# 5V0_SYS_SUPPLY.net
KiCad netlist of a schematic drawn in Altium Designer
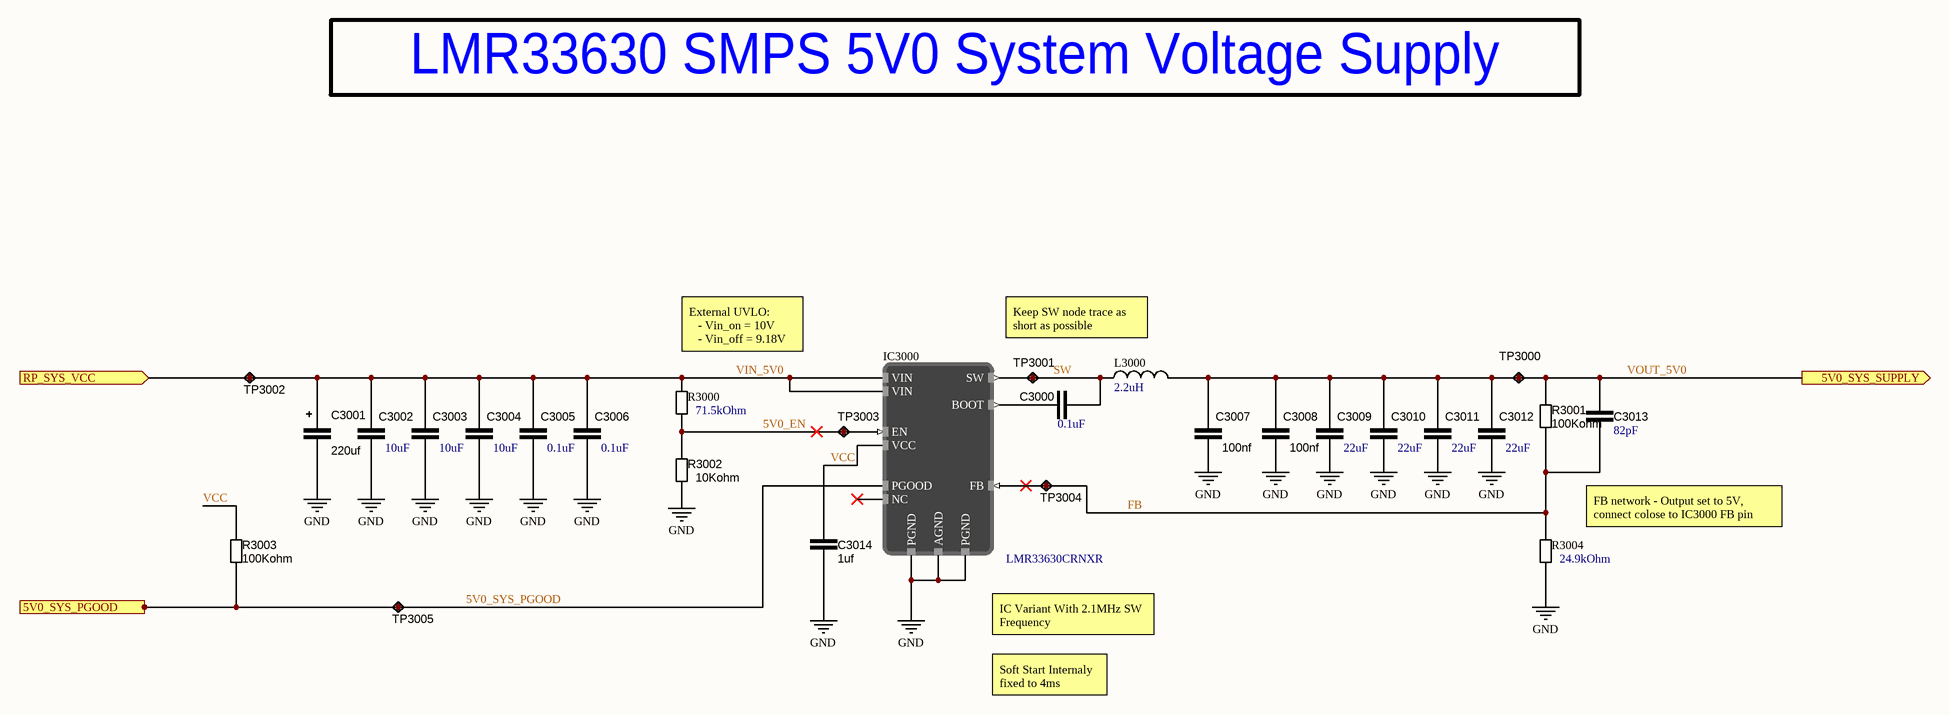
[diagram p0: 5V0_SYS_SUPPLY.SchDoc]

(export (version "E")
  (design (tool "Eeschema 10.0.6"))
  (components
    (comp (ref "C3000")
      (value "0.1uF")
      (footprint "CAP_0603")
      (description "CAP CER 0.1UF 50V X7R 0603")
      (fields (field (name "DIGIKEY PART NUMBER") "1276-1000-1-ND"))
      (libsource (lib "CapacitorsIntegrated") (part "C000018"))
    )
    (comp (ref "C3001")
      (value "220uf")
      (footprint "CAPAE109103X103M")
      (description "CAP ALUM 220UF 20% 50V SMD")
      (fields (field (name "DIGIKEY PART NUMBER") "493-9426-1-ND"))
      (libsource (lib "CapacitorsIntegrated") (part "C000019"))
    )
    (comp (ref "C3002")
      (value "10uF")
      (footprint "CAP_1206")
      (description "CAP CER 10UF 50V X7R 1206")
      (fields (field (name "DIGIKEY PART NUMBER") "1276-6767-1-ND"))
      (libsource (lib "CapacitorsIntegrated") (part "C000017"))
    )
    (comp (ref "C3003")
      (value "10uF")
      (footprint "CAP_1206")
      (description "CAP CER 10UF 50V X7R 1206")
      (fields (field (name "DIGIKEY PART NUMBER") "1276-6767-1-ND"))
      (libsource (lib "CapacitorsIntegrated") (part "C000017"))
    )
    (comp (ref "C3004")
      (value "10uF")
      (footprint "CAP_1206")
      (description "CAP CER 10UF 50V X7R 1206")
      (fields (field (name "DIGIKEY PART NUMBER") "1276-6767-1-ND"))
      (libsource (lib "CapacitorsIntegrated") (part "C000017"))
    )
    (comp (ref "C3005")
      (value "0.1uF")
      (footprint "CAP_0603")
      (description "CAP CER 0.1UF 50V X7R 0603")
      (fields (field (name "DIGIKEY PART NUMBER") "1276-1000-1-ND"))
      (libsource (lib "") (part "C000018_1"))
    )
    (comp (ref "C3006")
      (value "0.1uF")
      (footprint "CAP_0603")
      (description "CAP CER 0.1UF 50V X7R 0603")
      (fields (field (name "DIGIKEY PART NUMBER") "1276-1000-1-ND"))
      (libsource (lib "") (part "C000018_1"))
    )
    (comp (ref "C3007")
      (value "100nf")
      (footprint "CAP_0603")
      (description "CAP CER 100nF 0603 25V X7R")
      (libsource (lib "CapacitorsIntegrated") (part "C000007"))
    )
    (comp (ref "C3008")
      (value "100nf")
      (footprint "CAP_0603")
      (description "CAP CER 100nF 0603 25V X7R")
      (libsource (lib "CapacitorsIntegrated") (part "C000007"))
    )
    (comp (ref "C3009")
      (value "22uF")
      (footprint "CAP_1206")
      (description "22 µF ±10% 25V Ceramic Capacitor X5R 1206 (3216 Metric)")
      (fields (field (name "DIGIKEY PART NUMBER") "1276-3047-1-ND"))
      (libsource (lib "CapacitorsIntegrated") (part "C000020"))
    )
    (comp (ref "C3010")
      (value "22uF")
      (footprint "CAP_1206")
      (description "22 µF ±10% 25V Ceramic Capacitor X5R 1206 (3216 Metric)")
      (fields (field (name "DIGIKEY PART NUMBER") "1276-3047-1-ND"))
      (libsource (lib "CapacitorsIntegrated") (part "C000020"))
    )
    (comp (ref "C3011")
      (value "22uF")
      (footprint "CAP_1206")
      (description "22 µF ±10% 25V Ceramic Capacitor X5R 1206 (3216 Metric)")
      (fields (field (name "DIGIKEY PART NUMBER") "1276-3047-1-ND"))
      (libsource (lib "CapacitorsIntegrated") (part "C000020"))
    )
    (comp (ref "C3012")
      (value "22uF")
      (footprint "CAP_1206")
      (description "22 µF ±10% 25V Ceramic Capacitor X5R 1206 (3216 Metric)")
      (fields (field (name "DIGIKEY PART NUMBER") "1276-3047-1-ND"))
      (libsource (lib "CapacitorsIntegrated") (part "C000020"))
    )
    (comp (ref "C3013")
      (value "82pF")
      (footprint "CAP_0603")
      (description "82 pF ±1% 25V Ceramic Capacitor C0G, NP0 0603 (1608 Metric)")
      (fields (field (name "DIGIKEY PART NUMBER") "478-KGM15ACG1E820FTCT-ND"))
      (libsource (lib "CapacitorsIntegrated") (part "C000021"))
    )
    (comp (ref "C3014")
      (value "1uf")
      (footprint "CAP_0603")
      (description "CAP CER 1uF 10V X7R 0603")
      (fields (field (name "DIGIKEY PART NUMBER") "1276-1946-2-ND"))
      (libsource (lib "CapacitorsIntegrated") (part "C000011"))
    )
    (comp (ref "IC3000")
      (value "LMR33630CRNXR")
      (footprint "VQFN-HR")
      (description "Buck Switching Regulator IC Positive Adjustable 1V 1 Output 3A 12-PowerVFQFN")
      (fields
        (field (name "DIGIKEY PART NUMBER") "296-49768-1-ND")
        (field (name "MOUSER PART NUMBER") "595-LMR33630CRNXR")
      )
      (libsource (lib "IntegratedCircuits") (part "LMR33630CRNXR"))
    )
    (comp (ref "L3000")
      (value "2.2uH")
      (footprint "INDP_518X518")
      (description "FIXED IND 2.2UH 4.2A 50.1MOHM SM")
      (fields (field (name "DIGIKEY PART NUMBER") "541-1088-1-ND"))
      (libsource (lib "InductorIntegrated") (part "L000012"))
    )
    (comp (ref "R3000")
      (value "71.5kOhm")
      (footprint "RES_0603")
      (description "71.5 kOhms ±1% 0.1W, 1/10W Chip Resistor 0603 (1608 Metric) Moisture Resistant Thick Film")
      (fields (field (name "DIGIKEY PART NUMBER") "311-71.5KHRCT-ND"))
      (libsource (lib "ResistorsIntegrated") (part "R000022"))
    )
    (comp (ref "R3001")
      (value "100Kohm")
      (footprint "RES_0603")
      (description "RES 100K OHM 1% 1/10W 0603")
      (libsource (lib "ResistorsIntegrated") (part "R000006"))
    )
    (comp (ref "R3002")
      (value "10Kohm")
      (footprint "RES_0603")
      (description "RES 10K OHM 1% 1/10W 0603")
      (libsource (lib "ResistorsIntegrated") (part "R000001"))
    )
    (comp (ref "R3003")
      (value "100Kohm")
      (footprint "RES_0603")
      (description "RES 100K OHM 1% 1/10W 0603")
      (libsource (lib "ResistorsIntegrated") (part "R000006"))
    )
    (comp (ref "R3004")
      (value "24.9kOhm")
      (footprint "RES_0603")
      (description "24.9 kOhms ±1% 0.1W, 1/10W Chip Resistor 0603 (1608 Metric) Automotive AEC-Q200 Thick Film")
      (fields (field (name "DIGIKEY PART NUMBER") "P24.9KHCT-ND"))
      (libsource (lib "ResistorsIntegrated") (part "R000017"))
    )
    (comp (ref "TP3000")
      (value "Test point")
      (footprint "TestPoint")
      (description "Test point 1mm")
      (libsource (lib "IntegratedCircuits") (part "TP002"))
    )
    (comp (ref "TP3001")
      (value "Test point")
      (footprint "TestPoint")
      (description "Test point 1mm")
      (libsource (lib "IntegratedCircuits") (part "TP002"))
    )
    (comp (ref "TP3002")
      (value "Test point")
      (footprint "TestPoint")
      (description "Test point 1mm")
      (libsource (lib "IntegratedCircuits") (part "TP002"))
    )
    (comp (ref "TP3003")
      (value "Test point")
      (footprint "TestPoint")
      (description "Test point 1mm")
      (libsource (lib "IntegratedCircuits") (part "TP002"))
    )
    (comp (ref "TP3004")
      (value "Test point")
      (footprint "TestPoint")
      (description "Test point 1mm")
      (libsource (lib "IntegratedCircuits") (part "TP002"))
    )
    (comp (ref "TP3005")
      (value "Test point")
      (footprint "TestPoint")
      (description "Test point 1mm")
      (libsource (lib "IntegratedCircuits") (part "TP002"))
    )
  )
  (nets
    (net (code "1") (name "/5V0_EN") (class "Default")
      (node (ref "IC3000") (pin "9") (pinfunction "EN_9") (pintype "input"))
      (node (ref "R3000") (pin "1") (pinfunction "1_1") (pintype "passive"))
      (node (ref "R3002") (pin "2") (pinfunction "2_2") (pintype "passive"))
      (node (ref "TP3003") (pin "1") (pinfunction "1_1") (pintype "passive"))
    )
    (net (code "2") (name "/5V0_SYS_PGOOD") (class "Default")
      (node (ref "IC3000") (pin "8") (pinfunction "PGOOD_8") (pintype "open_collector"))
      (node (ref "R3003") (pin "1") (pinfunction "1_1") (pintype "passive"))
      (node (ref "TP3005") (pin "1") (pinfunction "1_1") (pintype "passive"))
    )
    (net (code "3") (name "/FB") (class "Default")
      (node (ref "C3013") (pin "1") (pinfunction "1_1") (pintype "passive"))
      (node (ref "IC3000") (pin "7") (pinfunction "FB_7") (pintype "input"))
      (node (ref "R3001") (pin "1") (pinfunction "1_1") (pintype "passive"))
      (node (ref "R3004") (pin "2") (pinfunction "2_2") (pintype "passive"))
      (node (ref "TP3004") (pin "1") (pinfunction "1_1") (pintype "passive"))
    )
    (net (code "4") (name "/SW") (class "Default")
      (node (ref "C3000") (pin "2") (pinfunction "2_2") (pintype "passive"))
      (node (ref "IC3000") (pin "12") (pinfunction "SW_12") (pintype "output"))
      (node (ref "L3000") (pin "1") (pinfunction "1_1") (pintype "passive"))
      (node (ref "TP3001") (pin "1") (pinfunction "1_1") (pintype "passive"))
    )
    (net (code "5") (name "/VCC") (class "Default")
      (node (ref "C3014") (pin "2") (pinfunction "2_2") (pintype "passive"))
      (node (ref "IC3000") (pin "5") (pinfunction "VCC_5") (pintype "power_in"))
      (node (ref "R3003") (pin "2") (pinfunction "2_2") (pintype "passive"))
    )
    (net (code "6") (name "/VIN_5V0") (class "Default")
      (node (ref "C3001") (pin "2") (pinfunction "2_2") (pintype "passive"))
      (node (ref "C3002") (pin "2") (pinfunction "2_2") (pintype "passive"))
      (node (ref "C3003") (pin "2") (pinfunction "2_2") (pintype "passive"))
      (node (ref "C3004") (pin "2") (pinfunction "2_2") (pintype "passive"))
      (node (ref "C3005") (pin "2") (pinfunction "2_2") (pintype "passive"))
      (node (ref "C3006") (pin "2") (pinfunction "2_2") (pintype "passive"))
      (node (ref "IC3000") (pin "10") (pinfunction "VIN_10") (pintype "passive"))
      (node (ref "IC3000") (pin "2") (pinfunction "VIN_2") (pintype "passive"))
      (node (ref "R3000") (pin "2") (pinfunction "2_2") (pintype "passive"))
      (node (ref "TP3002") (pin "1") (pinfunction "1_1") (pintype "passive"))
    )
    (net (code "7") (name "/VOUT_5V0") (class "Default")
      (node (ref "C3007") (pin "2") (pinfunction "2_2") (pintype "passive"))
      (node (ref "C3008") (pin "2") (pinfunction "2_2") (pintype "passive"))
      (node (ref "C3009") (pin "2") (pinfunction "2_2") (pintype "passive"))
      (node (ref "C3010") (pin "2") (pinfunction "2_2") (pintype "passive"))
      (node (ref "C3011") (pin "2") (pinfunction "2_2") (pintype "passive"))
      (node (ref "C3012") (pin "2") (pinfunction "2_2") (pintype "passive"))
      (node (ref "C3013") (pin "2") (pinfunction "2_2") (pintype "passive"))
      (node (ref "L3000") (pin "2") (pinfunction "2_2") (pintype "passive"))
      (node (ref "R3001") (pin "2") (pinfunction "2_2") (pintype "passive"))
      (node (ref "TP3000") (pin "1") (pinfunction "1_1") (pintype "passive"))
    )
    (net (code "8") (name "GND") (class "Default")
      (node (ref "C3001") (pin "1") (pinfunction "1_1") (pintype "passive"))
      (node (ref "C3002") (pin "1") (pinfunction "1_1") (pintype "passive"))
      (node (ref "C3003") (pin "1") (pinfunction "1_1") (pintype "passive"))
      (node (ref "C3004") (pin "1") (pinfunction "1_1") (pintype "passive"))
      (node (ref "C3005") (pin "1") (pinfunction "1_1") (pintype "passive"))
      (node (ref "C3006") (pin "1") (pinfunction "1_1") (pintype "passive"))
      (node (ref "C3007") (pin "1") (pinfunction "1_1") (pintype "passive"))
      (node (ref "C3008") (pin "1") (pinfunction "1_1") (pintype "passive"))
      (node (ref "C3009") (pin "1") (pinfunction "1_1") (pintype "passive"))
      (node (ref "C3010") (pin "1") (pinfunction "1_1") (pintype "passive"))
      (node (ref "C3011") (pin "1") (pinfunction "1_1") (pintype "passive"))
      (node (ref "C3012") (pin "1") (pinfunction "1_1") (pintype "passive"))
      (node (ref "C3014") (pin "1") (pinfunction "1_1") (pintype "passive"))
      (node (ref "IC3000") (pin "1") (pinfunction "PGND_1") (pintype "power_in"))
      (node (ref "IC3000") (pin "11") (pinfunction "PGND_11") (pintype "power_in"))
      (node (ref "IC3000") (pin "6") (pinfunction "AGND_6") (pintype "power_in"))
      (node (ref "R3002") (pin "1") (pinfunction "1_1") (pintype "passive"))
      (node (ref "R3004") (pin "1") (pinfunction "1_1") (pintype "passive"))
    )
    (net (code "9") (name "Net-(IC3000-BOOT)") (class "Default")
      (node (ref "C3000") (pin "1") (pinfunction "1_1") (pintype "passive"))
      (node (ref "IC3000") (pin "4") (pinfunction "BOOT_4") (pintype "output"))
    )
    (net (code "10") (name "unconnected-(IC3000-NC-Pad3)") (class "Default")
      (node (ref "IC3000") (pin "3") (pinfunction "NC_3") (pintype "tri_state+no_connect"))
    )
  )
)
